# MCU103A_F2800137_Device.net
KiCad netlist of a schematic drawn in Altium Designer
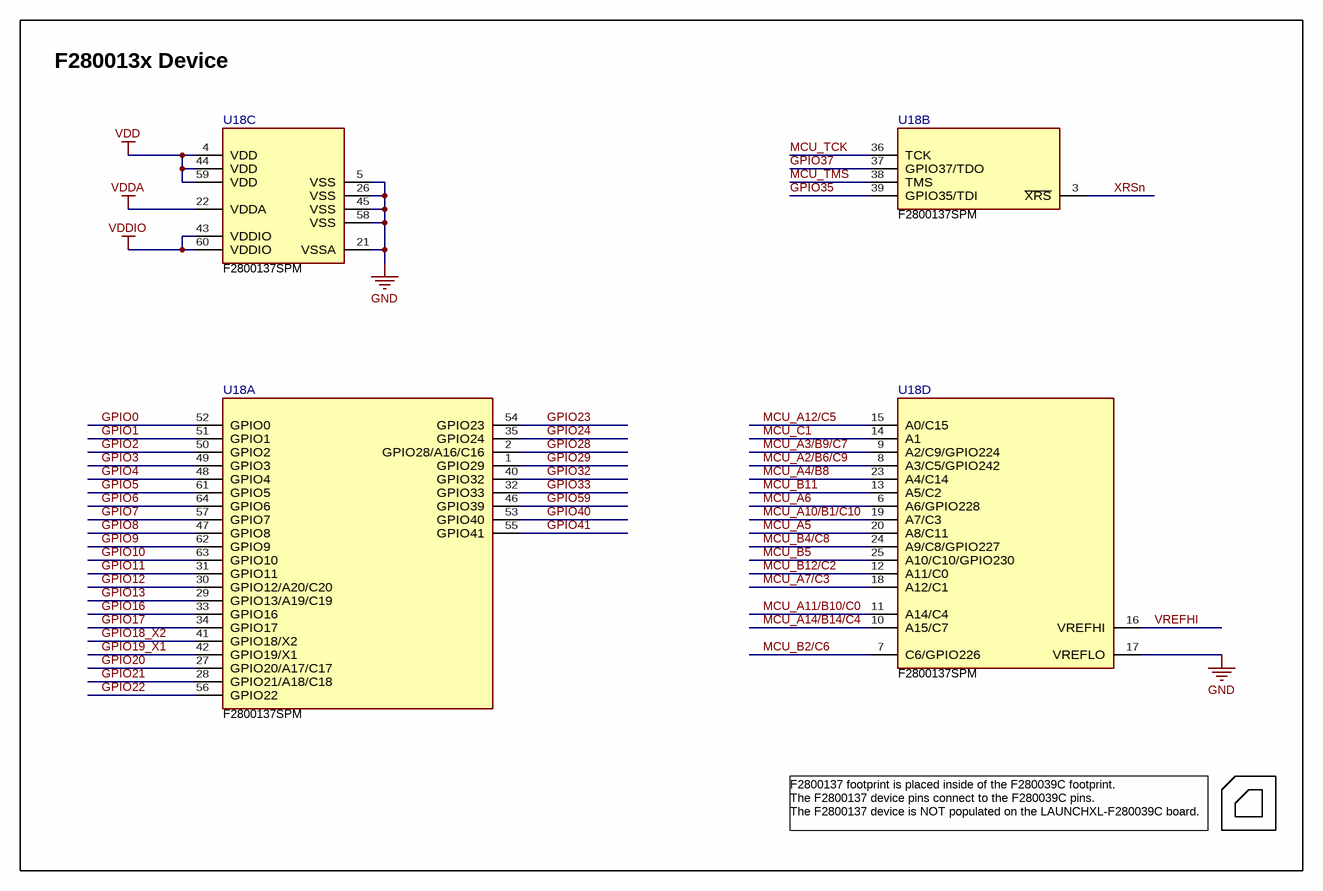
[diagram p0: MCU103A_F2800137_Device.SchDoc]

(export (version "E")
  (design (tool "Eeschema 10.0.6"))
  (components
    (comp (ref "U18")
      (value "F2800137SPM")
      (footprint "PM0064A-IPC_C")
      (fields (field (name "PARTNUMBER") "F2800137SPM") (field (name "MANUFACTURER") "Texas Instruments"))
      (libsource (lib "Altium Vault - TI") (part "SYM-F2800137SPM"))
    )
  )
  (nets
    (net (code "1") (name "/GPIO0") (class "Default")
      (node (ref "U18") (pin "52") (pinfunction "GPIO0_52") (pintype "passive"))
    )
    (net (code "2") (name "/GPIO1") (class "Default")
      (node (ref "U18") (pin "51") (pinfunction "GPIO1_51") (pintype "passive"))
    )
    (net (code "3") (name "/GPIO2") (class "Default")
      (node (ref "U18") (pin "50") (pinfunction "GPIO2_50") (pintype "passive"))
    )
    (net (code "4") (name "/GPIO3") (class "Default")
      (node (ref "U18") (pin "49") (pinfunction "GPIO3_49") (pintype "passive"))
    )
    (net (code "5") (name "/GPIO4") (class "Default")
      (node (ref "U18") (pin "48") (pinfunction "GPIO4_48") (pintype "passive"))
    )
    (net (code "6") (name "/GPIO5") (class "Default")
      (node (ref "U18") (pin "61") (pinfunction "GPIO5_61") (pintype "passive"))
    )
    (net (code "7") (name "/GPIO6") (class "Default")
      (node (ref "U18") (pin "64") (pinfunction "GPIO6_64") (pintype "passive"))
    )
    (net (code "8") (name "/GPIO7") (class "Default")
      (node (ref "U18") (pin "57") (pinfunction "GPIO7_57") (pintype "passive"))
    )
    (net (code "9") (name "/GPIO8") (class "Default")
      (node (ref "U18") (pin "47") (pinfunction "GPIO8_47") (pintype "passive"))
    )
    (net (code "10") (name "/GPIO9") (class "Default")
      (node (ref "U18") (pin "62") (pinfunction "GPIO9_62") (pintype "passive"))
    )
    (net (code "11") (name "/GPIO10") (class "Default")
      (node (ref "U18") (pin "63") (pinfunction "GPIO10_63") (pintype "passive"))
    )
    (net (code "12") (name "/GPIO11") (class "Default")
      (node (ref "U18") (pin "31") (pinfunction "GPIO11_31") (pintype "passive"))
    )
    (net (code "13") (name "/GPIO12") (class "Default")
      (node (ref "U18") (pin "30") (pinfunction "GPIO12/A20/C20_30") (pintype "passive"))
    )
    (net (code "14") (name "/GPIO13") (class "Default")
      (node (ref "U18") (pin "29") (pinfunction "GPIO13/A19/C19_29") (pintype "passive"))
    )
    (net (code "15") (name "/GPIO16") (class "Default")
      (node (ref "U18") (pin "33") (pinfunction "GPIO16_33") (pintype "passive"))
    )
    (net (code "16") (name "/GPIO17") (class "Default")
      (node (ref "U18") (pin "34") (pinfunction "GPIO17_34") (pintype "passive"))
    )
    (net (code "17") (name "/GPIO18_X2") (class "Default")
      (node (ref "U18") (pin "41") (pinfunction "GPIO18/X2_41") (pintype "passive"))
    )
    (net (code "18") (name "/GPIO19_X1") (class "Default")
      (node (ref "U18") (pin "42") (pinfunction "GPIO19/X1_42") (pintype "passive"))
    )
    (net (code "19") (name "/GPIO20") (class "Default")
      (node (ref "U18") (pin "27") (pinfunction "GPIO20/A17/C17_27") (pintype "passive"))
    )
    (net (code "20") (name "/GPIO21") (class "Default")
      (node (ref "U18") (pin "28") (pinfunction "GPIO21/A18/C18_28") (pintype "passive"))
    )
    (net (code "21") (name "/GPIO22") (class "Default")
      (node (ref "U18") (pin "56") (pinfunction "GPIO22_56") (pintype "passive"))
    )
    (net (code "22") (name "/GPIO23") (class "Default")
      (node (ref "U18") (pin "54") (pinfunction "GPIO23_54") (pintype "passive"))
    )
    (net (code "23") (name "/GPIO24") (class "Default")
      (node (ref "U18") (pin "35") (pinfunction "GPIO24_35") (pintype "passive"))
    )
    (net (code "24") (name "/GPIO28") (class "Default")
      (node (ref "U18") (pin "2") (pinfunction "GPIO28/A16/C16_2") (pintype "passive"))
    )
    (net (code "25") (name "/GPIO29") (class "Default")
      (node (ref "U18") (pin "1") (pinfunction "GPIO29_1") (pintype "passive"))
    )
    (net (code "26") (name "/GPIO32") (class "Default")
      (node (ref "U18") (pin "40") (pinfunction "GPIO32_40") (pintype "passive"))
    )
    (net (code "27") (name "/GPIO33") (class "Default")
      (node (ref "U18") (pin "32") (pinfunction "GPIO33_32") (pintype "passive"))
    )
    (net (code "28") (name "/GPIO35") (class "Default")
      (node (ref "U18") (pin "39") (pinfunction "GPIO35/TDI_39") (pintype "passive"))
    )
    (net (code "29") (name "/GPIO37") (class "Default")
      (node (ref "U18") (pin "37") (pinfunction "GPIO37/TDO_37") (pintype "passive"))
    )
    (net (code "30") (name "/GPIO40") (class "Default")
      (node (ref "U18") (pin "53") (pinfunction "GPIO40_53") (pintype "passive"))
    )
    (net (code "31") (name "/GPIO41") (class "Default")
      (node (ref "U18") (pin "55") (pinfunction "GPIO41_55") (pintype "passive"))
    )
    (net (code "32") (name "/GPIO59") (class "Default")
      (node (ref "U18") (pin "46") (pinfunction "GPIO39_46") (pintype "passive"))
    )
    (net (code "33") (name "/MCU_A2{slash}B6{slash}C9") (class "Default")
      (node (ref "U18") (pin "8") (pinfunction "A3/C5/GPIO242_8") (pintype "passive"))
    )
    (net (code "34") (name "/MCU_A3{slash}B9{slash}C7") (class "Default")
      (node (ref "U18") (pin "9") (pinfunction "A2/C9/GPIO224_9") (pintype "passive"))
    )
    (net (code "35") (name "/MCU_A4{slash}B8") (class "Default")
      (node (ref "U18") (pin "23") (pinfunction "A4/C14_23") (pintype "passive"))
    )
    (net (code "36") (name "/MCU_A5") (class "Default")
      (node (ref "U18") (pin "20") (pinfunction "A8/C11_20") (pintype "passive"))
    )
    (net (code "37") (name "/MCU_A6") (class "Default")
      (node (ref "U18") (pin "6") (pinfunction "A6/GPIO228_6") (pintype "passive"))
    )
    (net (code "38") (name "/MCU_A7{slash}C3") (class "Default")
      (node (ref "U18") (pin "18") (pinfunction "A12/C1_18") (pintype "passive"))
    )
    (net (code "39") (name "/MCU_A10{slash}B1{slash}C10") (class "Default")
      (node (ref "U18") (pin "19") (pinfunction "A7/C3_19") (pintype "passive"))
    )
    (net (code "40") (name "/MCU_A11{slash}B10{slash}C0") (class "Default")
      (node (ref "U18") (pin "11") (pinfunction "A14/C4_11") (pintype "passive"))
    )
    (net (code "41") (name "/MCU_A12{slash}C5") (class "Default")
      (node (ref "U18") (pin "15") (pinfunction "A0/C15_15") (pintype "passive"))
    )
    (net (code "42") (name "/MCU_A14{slash}B14{slash}C4") (class "Default")
      (node (ref "U18") (pin "10") (pinfunction "A15/C7_10") (pintype "passive"))
    )
    (net (code "43") (name "/MCU_B2{slash}C6") (class "Default")
      (node (ref "U18") (pin "7") (pinfunction "C6/GPIO226_7") (pintype "passive"))
    )
    (net (code "44") (name "/MCU_B4{slash}C8") (class "Default")
      (node (ref "U18") (pin "24") (pinfunction "A9/C8/GPIO227_24") (pintype "passive"))
    )
    (net (code "45") (name "/MCU_B5") (class "Default")
      (node (ref "U18") (pin "25") (pinfunction "A10/C10/GPIO230_25") (pintype "passive"))
    )
    (net (code "46") (name "/MCU_B11") (class "Default")
      (node (ref "U18") (pin "13") (pinfunction "A5/C2_13") (pintype "passive"))
    )
    (net (code "47") (name "/MCU_B12{slash}C2") (class "Default")
      (node (ref "U18") (pin "12") (pinfunction "A11/C0_12") (pintype "passive"))
    )
    (net (code "48") (name "/MCU_C1") (class "Default")
      (node (ref "U18") (pin "14") (pinfunction "A1_14") (pintype "passive"))
    )
    (net (code "49") (name "/MCU_TCK") (class "Default")
      (node (ref "U18") (pin "36") (pinfunction "TCK_36") (pintype "passive"))
    )
    (net (code "50") (name "/MCU_TMS") (class "Default")
      (node (ref "U18") (pin "38") (pinfunction "TMS_38") (pintype "passive"))
    )
    (net (code "51") (name "/VREFHI") (class "Default")
      (node (ref "U18") (pin "16") (pinfunction "VREFHI_16") (pintype "passive"))
    )
    (net (code "52") (name "/XRSn") (class "Default")
      (node (ref "U18") (pin "3") (pinfunction "~{XRS}_3") (pintype "passive"))
    )
    (net (code "53") (name "GND") (class "Default")
      (node (ref "U18") (pin "17") (pinfunction "VREFLO_17") (pintype "passive"))
      (node (ref "U18") (pin "21") (pinfunction "VSSA_21") (pintype "passive"))
      (node (ref "U18") (pin "26") (pinfunction "VSS_26") (pintype "passive"))
      (node (ref "U18") (pin "45") (pinfunction "VSS_45") (pintype "passive"))
      (node (ref "U18") (pin "5") (pinfunction "VSS_5") (pintype "passive"))
      (node (ref "U18") (pin "58") (pinfunction "VSS_58") (pintype "passive"))
    )
    (net (code "54") (name "VDD") (class "Default")
      (node (ref "U18") (pin "4") (pinfunction "VDD_4") (pintype "passive"))
      (node (ref "U18") (pin "44") (pinfunction "VDD_44") (pintype "passive"))
      (node (ref "U18") (pin "59") (pinfunction "VDD_59") (pintype "passive"))
    )
    (net (code "55") (name "VDDA") (class "Default")
      (node (ref "U18") (pin "22") (pinfunction "VDDA_22") (pintype "passive"))
    )
    (net (code "56") (name "VDDIO") (class "Default")
      (node (ref "U18") (pin "43") (pinfunction "VDDIO_43") (pintype "passive"))
      (node (ref "U18") (pin "60") (pinfunction "VDDIO_60") (pintype "passive"))
    )
  )
)
